# mLRS-rx-tx-E77-E28-dualband-easysolder-v.net
KiCad netlist of a schematic drawn in EAGLE
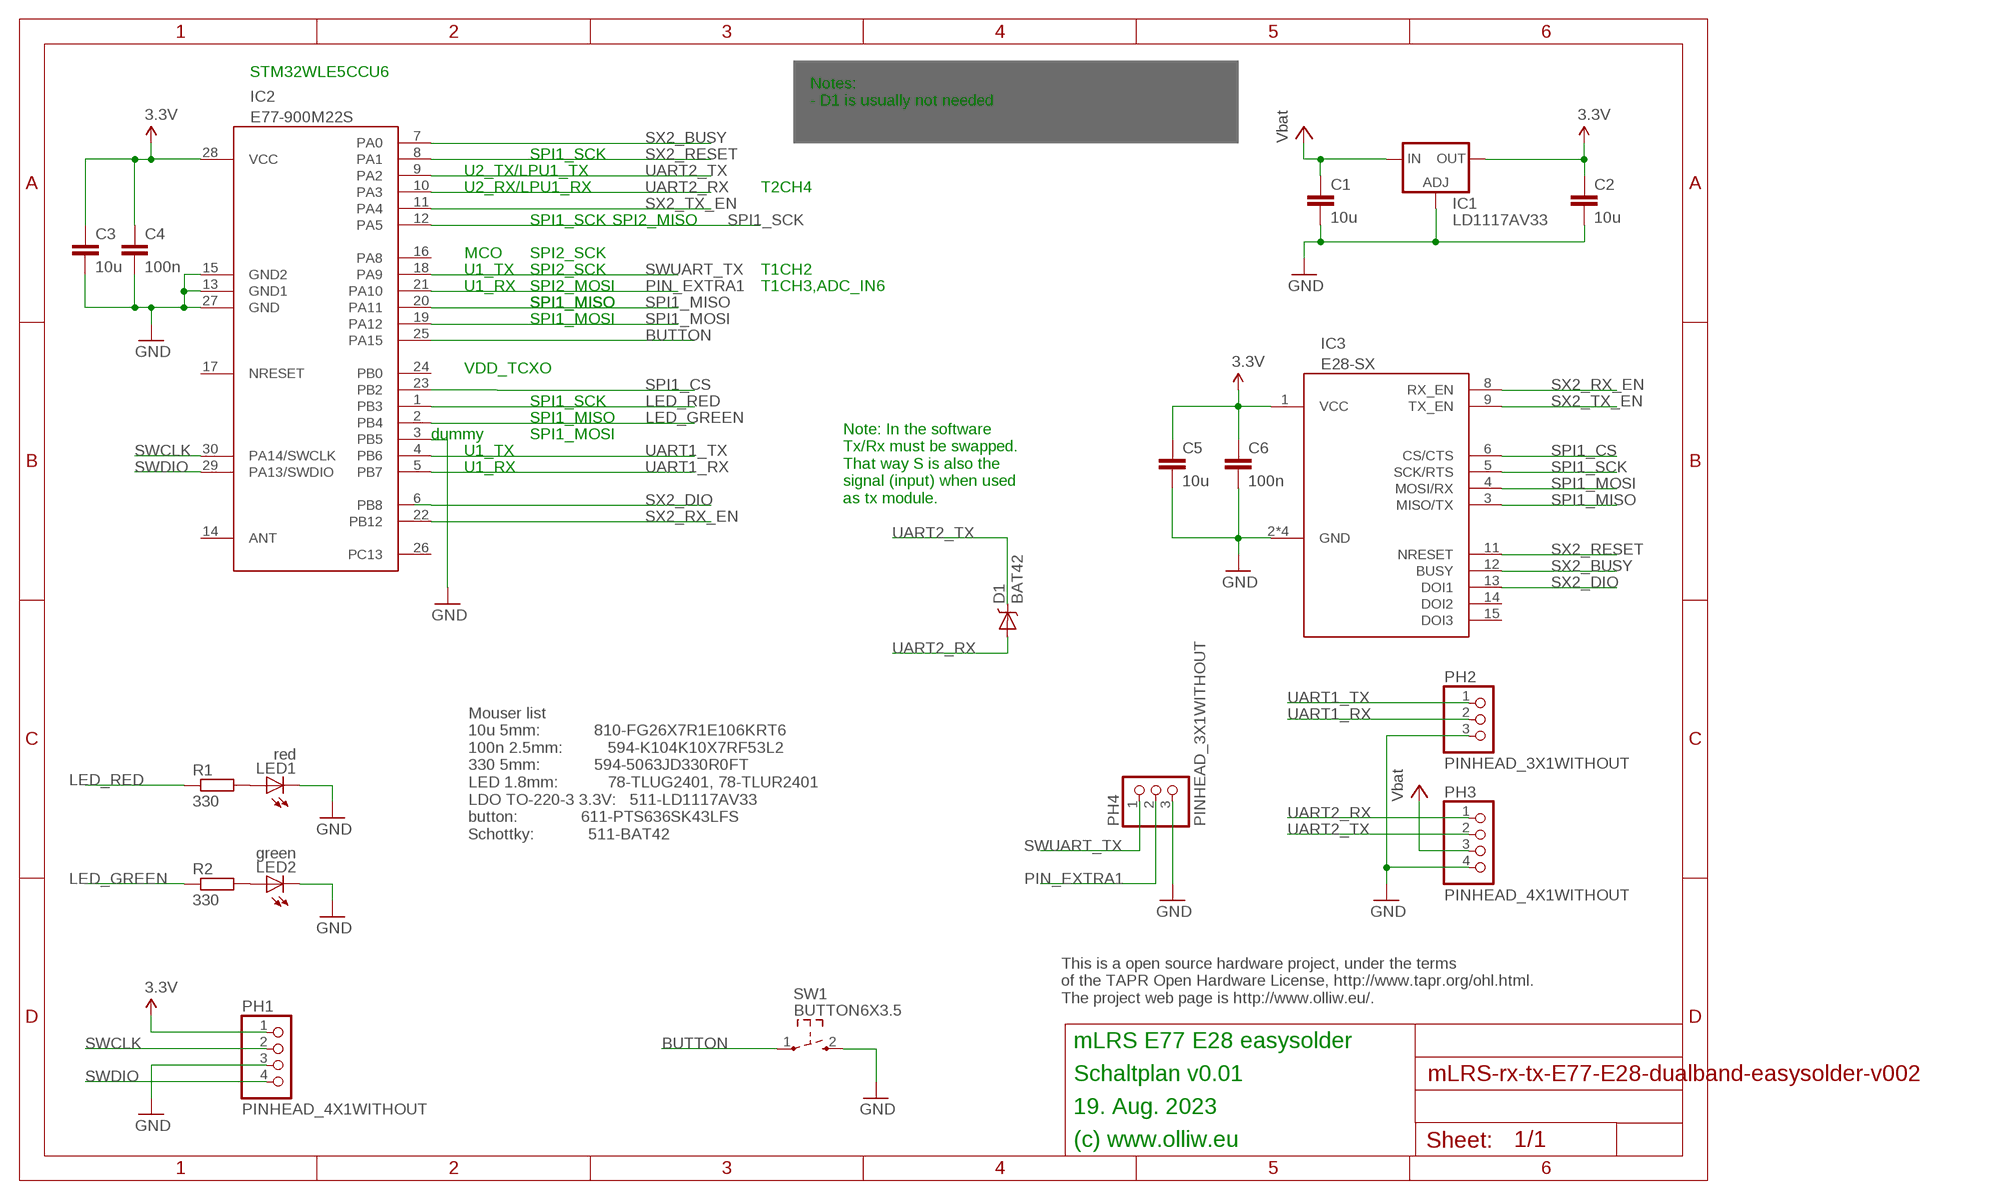
[diagram p0: schematic, sheet 1]

(export (version "E")
  (design (tool "Eeschema 10.0.6"))
  (components
    (comp (ref "C1")
      (value "10u")
      (footprint "eagle-import:C050-045X075")
      (libsource (lib "eagle-import") (part "C-EU050-045X075"))
    )
    (comp (ref "C2")
      (value "10u")
      (footprint "eagle-import:C050-045X075")
      (libsource (lib "eagle-import") (part "C-EU050-045X075"))
    )
    (comp (ref "C3")
      (value "10u")
      (footprint "eagle-import:C050-024X044")
      (libsource (lib "eagle-import") (part "C-EU050-024X044"))
    )
    (comp (ref "C4")
      (value "100n")
      (footprint "eagle-import:C025-024X044")
      (libsource (lib "eagle-import") (part "C-EU025-024X044"))
    )
    (comp (ref "C5")
      (value "10u")
      (footprint "eagle-import:C050-024X044")
      (libsource (lib "eagle-import") (part "C-EU050-024X044"))
    )
    (comp (ref "C6")
      (value "100n")
      (footprint "eagle-import:C025-024X044")
      (libsource (lib "eagle-import") (part "C-EU025-024X044"))
    )
    (comp (ref "D1")
      (value "BAT42")
      (footprint "eagle-import:D_7.5")
      (libsource (lib "eagle-import") (part "DIODE-SCHOTTKY7.62MM"))
    )
    (comp (ref "IC1")
      (value "LD1117AV33")
      (footprint "eagle-import:TO220L1")
      (libsource (lib "eagle-import") (part "LD117A?V33"))
    )
    (comp (ref "IC2")
      (value "E77-900M22S")
      (footprint "eagle-import:E77-900M22S")
      (libsource (lib "eagle-import") (part "E77-900M22S"))
    )
    (comp (ref "IC3")
      (value "E28-SX")
      (footprint "eagle-import:E28-2G4M27SX")
      (libsource (lib "eagle-import") (part "E28-SX"))
    )
    (comp (ref "LED1")
      (value "red")
      (footprint "eagle-import:LED1.8MM")
      (libsource (lib "eagle-import") (part "LED1.8MM"))
    )
    (comp (ref "LED2")
      (value "green")
      (footprint "eagle-import:LED1.8MM")
      (libsource (lib "eagle-import") (part "LED1.8MM"))
    )
    (comp (ref "PH1")
      (value "PINHEAD_4X1WITHOUT")
      (footprint "eagle-import:PINHEAD_4X1_WO")
      (libsource (lib "eagle-import") (part "PINHEAD_4X1WITHOUT"))
    )
    (comp (ref "PH2")
      (value "PINHEAD_3X1WITHOUT")
      (footprint "eagle-import:PINHEAD_3X1_WO")
      (libsource (lib "eagle-import") (part "PINHEAD_3X1WITHOUT"))
    )
    (comp (ref "PH3")
      (value "PINHEAD_4X1WITHOUT")
      (footprint "eagle-import:PINHEAD_4X1_WO")
      (libsource (lib "eagle-import") (part "PINHEAD_4X1WITHOUT"))
    )
    (comp (ref "PH4")
      (value "PINHEAD_3X1WITHOUT")
      (footprint "eagle-import:PINHEAD_3X1_WO")
      (libsource (lib "eagle-import") (part "PINHEAD_3X1WITHOUT"))
    )
    (comp (ref "R1")
      (value "330")
      (footprint "eagle-import:R0204_6.25")
      (libsource (lib "eagle-import") (part "R_EUR0204/6.25"))
    )
    (comp (ref "R2")
      (value "330")
      (footprint "eagle-import:R0204_6.25")
      (libsource (lib "eagle-import") (part "R_EUR0204/6.25"))
    )
    (comp (ref "SW1")
      (value "BUTTON6X3.5")
      (footprint "eagle-import:BUTTON-THT")
      (libsource (lib "eagle-import") (part "BUTTON6X3.5"))
    )
  )
  (nets
    (net (code "1") (name "/BUTTON") (class "Default")
      (node (ref "IC2") (pin "25") (pinfunction "PA15_25") (pintype "bidirectional"))
      (node (ref "SW1") (pin "1") (pinfunction "1_1") (pintype "passive"))
    )
    (net (code "2") (name "/LED_GREEN") (class "Default")
      (node (ref "IC2") (pin "2") (pinfunction "PB4_2") (pintype "bidirectional"))
      (node (ref "R2") (pin "1") (pinfunction "1_1") (pintype "passive"))
    )
    (net (code "3") (name "/LED_RED") (class "Default")
      (node (ref "IC2") (pin "1") (pinfunction "PB3_1") (pintype "bidirectional"))
      (node (ref "R1") (pin "1") (pinfunction "1_1") (pintype "passive"))
    )
    (net (code "4") (name "/PIN_EXTRA1") (class "Default")
      (node (ref "IC2") (pin "21") (pinfunction "PA10_21") (pintype "bidirectional"))
      (node (ref "PH4") (pin "2") (pinfunction "3_2") (pintype "passive"))
    )
    (net (code "5") (name "/SPI1_CS") (class "Default")
      (node (ref "IC2") (pin "23") (pinfunction "PB2_23") (pintype "bidirectional"))
      (node (ref "IC3") (pin "6") (pinfunction "CS/CTS_6") (pintype "bidirectional"))
    )
    (net (code "6") (name "/SPI1_MISO") (class "Default")
      (node (ref "IC2") (pin "20") (pinfunction "PA11_20") (pintype "bidirectional"))
      (node (ref "IC3") (pin "3") (pinfunction "MISO/TX_3") (pintype "bidirectional"))
    )
    (net (code "7") (name "/SPI1_MOSI") (class "Default")
      (node (ref "IC2") (pin "19") (pinfunction "PA12_19") (pintype "bidirectional"))
      (node (ref "IC3") (pin "4") (pinfunction "MOSI/RX_4") (pintype "bidirectional"))
    )
    (net (code "8") (name "/SPI1_SCK") (class "Default")
      (node (ref "IC2") (pin "12") (pinfunction "PA5_12") (pintype "bidirectional"))
      (node (ref "IC3") (pin "5") (pinfunction "SCK/RTS_5") (pintype "bidirectional"))
    )
    (net (code "9") (name "/SWCLK") (class "Default")
      (node (ref "IC2") (pin "30") (pinfunction "PA14/SWCLK_30") (pintype "bidirectional"))
      (node (ref "PH1") (pin "2") (pinfunction "2_2") (pintype "passive"))
    )
    (net (code "10") (name "/SWDIO") (class "Default")
      (node (ref "IC2") (pin "29") (pinfunction "PA13/SWDIO_29") (pintype "bidirectional"))
      (node (ref "PH1") (pin "4") (pinfunction "4_4") (pintype "passive"))
    )
    (net (code "11") (name "/SWUART_TX") (class "Default")
      (node (ref "IC2") (pin "18") (pinfunction "PA9_18") (pintype "bidirectional"))
      (node (ref "PH4") (pin "1") (pinfunction "1_1") (pintype "passive"))
    )
    (net (code "12") (name "/SX2_BUSY") (class "Default")
      (node (ref "IC2") (pin "7") (pinfunction "PA0_7") (pintype "bidirectional"))
      (node (ref "IC3") (pin "12") (pinfunction "BUSY_12") (pintype "bidirectional"))
    )
    (net (code "13") (name "/SX2_DIO") (class "Default")
      (node (ref "IC2") (pin "6") (pinfunction "PB8_6") (pintype "bidirectional"))
      (node (ref "IC3") (pin "13") (pinfunction "DOI1_13") (pintype "bidirectional"))
    )
    (net (code "14") (name "/SX2_RESET") (class "Default")
      (node (ref "IC2") (pin "8") (pinfunction "PA1_8") (pintype "bidirectional"))
      (node (ref "IC3") (pin "11") (pinfunction "NRESET_11") (pintype "input"))
    )
    (net (code "15") (name "/SX2_RX_EN") (class "Default")
      (node (ref "IC2") (pin "22") (pinfunction "PB12_22") (pintype "bidirectional"))
      (node (ref "IC3") (pin "8") (pinfunction "RX_EN_8") (pintype "bidirectional"))
    )
    (net (code "16") (name "/SX2_TX_EN") (class "Default")
      (node (ref "IC2") (pin "11") (pinfunction "PA4_11") (pintype "bidirectional"))
      (node (ref "IC3") (pin "9") (pinfunction "TX_EN_9") (pintype "bidirectional"))
    )
    (net (code "17") (name "/UART1_RX") (class "Default")
      (node (ref "IC2") (pin "5") (pinfunction "PB7_5") (pintype "bidirectional"))
      (node (ref "PH2") (pin "2") (pinfunction "3_2") (pintype "passive"))
    )
    (net (code "18") (name "/UART1_TX") (class "Default")
      (node (ref "IC2") (pin "4") (pinfunction "PB6_4") (pintype "bidirectional"))
      (node (ref "PH2") (pin "1") (pinfunction "1_1") (pintype "passive"))
    )
    (net (code "19") (name "/UART2_RX") (class "Default")
      (node (ref "D1") (pin "A") (pinfunction "A_A") (pintype "passive"))
      (node (ref "IC2") (pin "10") (pinfunction "PA3_10") (pintype "bidirectional"))
      (node (ref "PH3") (pin "1") (pinfunction "1_1") (pintype "passive"))
    )
    (net (code "20") (name "/UART2_TX") (class "Default")
      (node (ref "D1") (pin "C") (pinfunction "C_C") (pintype "passive"))
      (node (ref "IC2") (pin "9") (pinfunction "PA2_9") (pintype "bidirectional"))
      (node (ref "PH3") (pin "2") (pinfunction "2_2") (pintype "passive"))
    )
    (net (code "21") (name "3.3V") (class "Default")
      (node (ref "C2") (pin "1") (pinfunction "1_1") (pintype "passive"))
      (node (ref "C3") (pin "1") (pinfunction "1_1") (pintype "passive"))
      (node (ref "C4") (pin "1") (pinfunction "1_1") (pintype "passive"))
      (node (ref "C5") (pin "1") (pinfunction "1_1") (pintype "passive"))
      (node (ref "C6") (pin "1") (pinfunction "1_1") (pintype "passive"))
      (node (ref "IC1") (pin "2") (pinfunction "OUT_2") (pintype "passive"))
      (node (ref "IC2") (pin "28") (pinfunction "VCC_28") (pintype "power_in"))
      (node (ref "IC3") (pin "1") (pinfunction "VCC_1") (pintype "power_in"))
      (node (ref "PH1") (pin "1") (pinfunction "1_1") (pintype "passive"))
    )
    (net (code "22") (name "GND") (class "Default")
      (node (ref "C1") (pin "2") (pinfunction "2_2") (pintype "passive"))
      (node (ref "C2") (pin "2") (pinfunction "2_2") (pintype "passive"))
      (node (ref "C3") (pin "2") (pinfunction "2_2") (pintype "passive"))
      (node (ref "C4") (pin "2") (pinfunction "2_2") (pintype "passive"))
      (node (ref "C5") (pin "2") (pinfunction "2_2") (pintype "passive"))
      (node (ref "C6") (pin "2") (pinfunction "2_2") (pintype "passive"))
      (node (ref "IC1") (pin "1") (pinfunction "ADJ_1") (pintype "input"))
      (node (ref "IC2") (pin "13") (pinfunction "GND1_13") (pintype "power_in"))
      (node (ref "IC2") (pin "15") (pinfunction "GND2_15") (pintype "power_in"))
      (node (ref "IC2") (pin "27") (pinfunction "GND_27") (pintype "power_in"))
      (node (ref "IC2") (pin "3") (pinfunction "PB5_3") (pintype "bidirectional"))
      (node (ref "IC3") (pin "10") (pinfunction "GND_10") (pintype "power_in"))
      (node (ref "IC3") (pin "16") (pinfunction "GND_16") (pintype "power_in"))
      (node (ref "IC3") (pin "2") (pinfunction "GND_2") (pintype "power_in"))
      (node (ref "IC3") (pin "7") (pinfunction "GND_7") (pintype "power_in"))
      (node (ref "LED1") (pin "K") (pinfunction "C_K") (pintype "passive"))
      (node (ref "LED2") (pin "K") (pinfunction "C_K") (pintype "passive"))
      (node (ref "PH1") (pin "3") (pinfunction "3_3") (pintype "passive"))
      (node (ref "PH2") (pin "3") (pinfunction "5_3") (pintype "passive"))
      (node (ref "PH3") (pin "4") (pinfunction "4_4") (pintype "passive"))
      (node (ref "PH4") (pin "3") (pinfunction "5_3") (pintype "passive"))
      (node (ref "SW1") (pin "2") (pinfunction "3_2") (pintype "passive"))
    )
    (net (code "23") (name "Net-(LED1-PadA)") (class "Default")
      (node (ref "LED1") (pin "A") (pinfunction "A_A") (pintype "passive"))
      (node (ref "R1") (pin "2") (pinfunction "2_2") (pintype "passive"))
    )
    (net (code "24") (name "Net-(LED2-PadA)") (class "Default")
      (node (ref "LED2") (pin "A") (pinfunction "A_A") (pintype "passive"))
      (node (ref "R2") (pin "2") (pinfunction "2_2") (pintype "passive"))
    )
    (net (code "25") (name "Vbat") (class "Default")
      (node (ref "C1") (pin "1") (pinfunction "1_1") (pintype "passive"))
      (node (ref "IC1") (pin "3") (pinfunction "IN_3") (pintype "input"))
      (node (ref "PH3") (pin "3") (pinfunction "3_3") (pintype "passive"))
    )
    (net (code "26") (name "unconnected-(IC2-ANT-Pad14)") (class "Default")
      (node (ref "IC2") (pin "14") (pinfunction "ANT_14") (pintype "bidirectional"))
    )
    (net (code "27") (name "unconnected-(IC2-NRESET-Pad17)") (class "Default")
      (node (ref "IC2") (pin "17") (pinfunction "NRESET_17") (pintype "input"))
    )
    (net (code "28") (name "unconnected-(IC2-PA8-Pad16)") (class "Default")
      (node (ref "IC2") (pin "16") (pinfunction "PA8_16") (pintype "bidirectional"))
    )
    (net (code "29") (name "unconnected-(IC2-PB0-Pad24)") (class "Default")
      (node (ref "IC2") (pin "24") (pinfunction "PB0_24") (pintype "bidirectional"))
    )
    (net (code "30") (name "unconnected-(IC2-PC13-Pad26)") (class "Default")
      (node (ref "IC2") (pin "26") (pinfunction "PC13_26") (pintype "bidirectional"))
    )
    (net (code "31") (name "unconnected-(IC3-DOI2-Pad14)") (class "Default")
      (node (ref "IC3") (pin "14") (pinfunction "DOI2_14") (pintype "bidirectional"))
    )
    (net (code "32") (name "unconnected-(IC3-DOI3-Pad15)") (class "Default")
      (node (ref "IC3") (pin "15") (pinfunction "DOI3_15") (pintype "bidirectional"))
    )
  )
)
